# CON1.net
KiCad netlist of a schematic drawn in Altium Designer
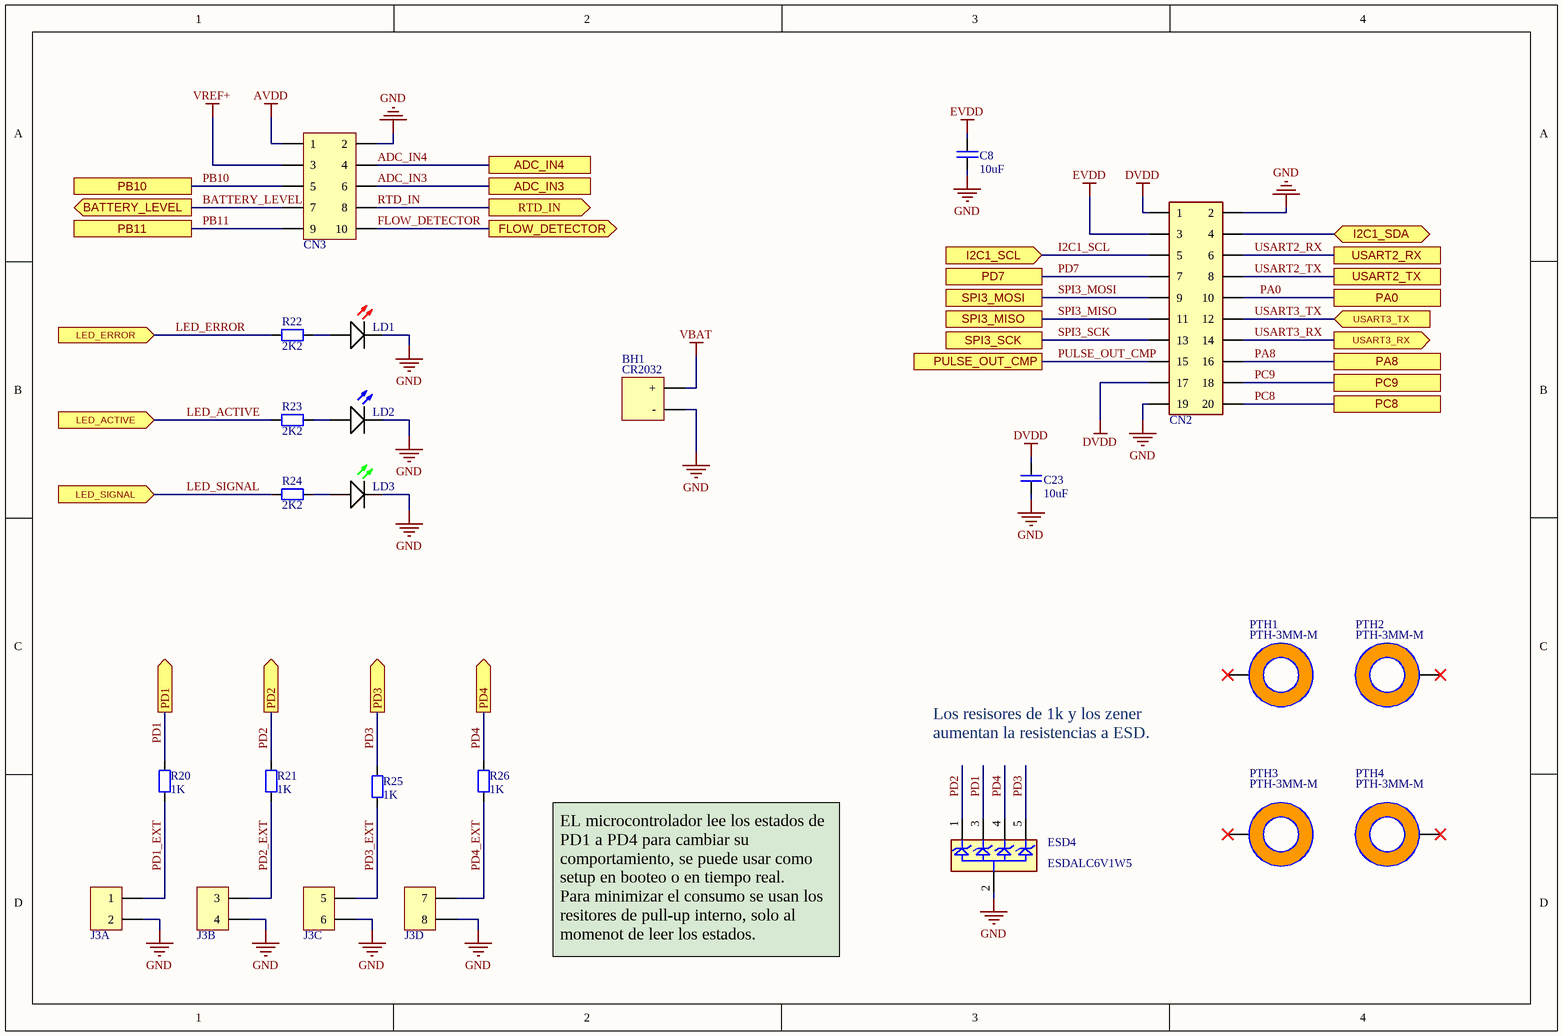
[diagram p0: CON1.SchDoc]

(export (version "E")
  (design (tool "Eeschema 10.0.6"))
  (components
    (comp (ref "BH1")
      (value "CR2032")
      (footprint "BS-08-B2AA016")
      (description "Battery base -25℃~+85℃ CR2032 SMD Battery Connectors ROHS")
      (fields
        (field (name "MANUFACTURER") "Myoung")
        (field (name "MANUFACTURER PART NUMBER") "BS-08-B2AA016")
      )
      (libsource (lib "Battery_Holders") (part "BS-08-B2AA016"))
    )
    (comp (ref "C8")
      (value "10uF")
      (footprint "CAP_SM0805_YAGEOCC2_N")
      (description "CAP 10uF SM0805 X5R 25V YAGEO")
      (fields
        (field (name "MANUFACTURER") "Yageo")
        (field (name "MANUFACTURER PART NUMBER") "CC0805KKX5R8BB106")
      )
      (libsource (lib "Yageo") (part "CC0805KKX5R8BB106"))
    )
    (comp (ref "C23")
      (value "10uF")
      (footprint "CAP_SM0805_YAGEOCC2_N")
      (description "CAP 10uF SM0805 X5R 25V YAGEO")
      (fields
        (field (name "MANUFACTURER") "Yageo")
        (field (name "MANUFACTURER PART NUMBER") "CC0805KKX5R8BB106")
      )
      (libsource (lib "Yageo") (part "CC0805KKX5R8BB106"))
    )
    (comp (ref "CN2")
      (value "DW254R-22-20-85")
      (footprint "DW254R-22-10-85")
      (description "2 x 10 - true hole 2.54mm - altura 8.5mm")
      (fields (field (name "MANUFACTURER") "Dealon"))
      (libsource (lib "header_female") (part "DW254R-22-20-85"))
    )
    (comp (ref "CN3")
      (value "DW254S-22-10-85")
      (footprint "2X5 100 MILS SMD")
      (description "2 x 5 - SMD 2.54mm - altura 8.5mm")
      (fields (field (name "MANUFACTURER") "Dealon"))
      (libsource (lib "header_female") (part "DW254S-22-10-85"))
    )
    (comp (ref "ESD4")
      (value "ESDALC6V1W5")
      (footprint "ESDALC6V1W5")
      (fields (field (name "MANUFACTURER") "ST"))
      (libsource (lib "diode") (part "ESDALC6V1W5"))
    )
    (comp (ref "J3")
      (value "PH2.54-07-04PWS-JUMPER")
      (footprint "HEADER PIN 2X4 A 90 GRADOS")
      (description "2 x 4 - true hole  2.54mm 90°")
      (fields
        (field (name "MANUFACTURER") "XUNPU")
        (field (name "MANUFACTURER PART NUMBER") "PH2.54-07-04PWS")
      )
      (libsource (lib "header_pin") (part "PH2.54-07-04PWS-JUMPER"))
    )
    (comp (ref "LD1")
      (value "ERROR")
      (footprint "LED 0805")
      (fields
        (field (name "MANUFACTURER") "Everlight Elec")
        (field (name "MANUFACTURER PART NUMBER") "17-21SURC/S530-A2/TR8")
      )
      (libsource (lib "LED") (part "17-21SURC/S530-A2/TR8"))
    )
    (comp (ref "LD2")
      (value "RUN")
      (footprint "LED 0805")
      (fields
        (field (name "MANUFACTURER") "Everlight Elec")
        (field (name "MANUFACTURER PART NUMBER") "17-21/BHC-XL2M2TY")
      )
      (libsource (lib "LED") (part "17-21/BHC-XL2M2TY/3T"))
    )
    (comp (ref "LD3")
      (value "SGINAL")
      (footprint "LED 0805")
      (fields
        (field (name "MANUFACTURER") "Everlight Elec")
        (field (name "MANUFACTURER PART NUMBER") "17-21SYGC/S530-E2/TR8")
      )
      (libsource (lib "LED") (part "17-21SYGC/S530-E2/TR8"))
    )
    (comp (ref "PTH1")
      (value "PTH-3MM-M")
      (footprint "PTH_M3_M")
      (description "Agujero de montaje metalizado roscas M3. Drill de tamaño medio.")
      (libsource (lib "montaje") (part "PTH-3MM-M"))
    )
    (comp (ref "PTH2")
      (value "PTH-3MM-M")
      (footprint "PTH_M3_M")
      (description "Agujero de montaje metalizado roscas M3. Drill de tamaño medio.")
      (libsource (lib "montaje") (part "PTH-3MM-M"))
    )
    (comp (ref "PTH3")
      (value "PTH-3MM-M")
      (footprint "PTH_M3_M")
      (description "Agujero de montaje metalizado roscas M3. Drill de tamaño medio.")
      (libsource (lib "montaje") (part "PTH-3MM-M"))
    )
    (comp (ref "PTH4")
      (value "PTH-3MM-M")
      (footprint "PTH_M3_M")
      (description "Agujero de montaje metalizado roscas M3. Drill de tamaño medio.")
      (libsource (lib "montaje") (part "PTH-3MM-M"))
    )
    (comp (ref "R20")
      (value "1K")
      (footprint "RES_SM0805_YAGEORC_N")
      (description "RES 1K SM0805 YAGEO RC_L")
      (fields
        (field (name "MANUFACTURER") "Yageo")
        (field (name "MANUFACTURER PART NUMBER") "RC0805FR-071KL")
      )
      (libsource (lib "Yageo") (part "RC0805FR-071KL"))
    )
    (comp (ref "R21")
      (value "1K")
      (footprint "RES_SM0805_YAGEORC_N")
      (description "RES 1K SM0805 YAGEO RC_L")
      (fields
        (field (name "MANUFACTURER") "Yageo")
        (field (name "MANUFACTURER PART NUMBER") "RC0805FR-071KL")
      )
      (libsource (lib "Yageo") (part "RC0805FR-071KL"))
    )
    (comp (ref "R22")
      (value "2K2")
      (footprint "RES_SM0805_YAGEORC_N")
      (description "RES 2K2 SM0805 YAGEO RC_L")
      (fields
        (field (name "MANUFACTURER") "Yageo")
        (field (name "MANUFACTURER PART NUMBER") "RC0805FR-072K2L")
      )
      (libsource (lib "Yageo") (part "RC0805FR-072K2L"))
    )
    (comp (ref "R23")
      (value "2K2")
      (footprint "RES_SM0805_YAGEORC_N")
      (description "RES 2K2 SM0805 YAGEO RC_L")
      (fields
        (field (name "MANUFACTURER") "Yageo")
        (field (name "MANUFACTURER PART NUMBER") "RC0805FR-072K2L")
      )
      (libsource (lib "Yageo") (part "RC0805FR-072K2L"))
    )
    (comp (ref "R24")
      (value "2K2")
      (footprint "RES_SM0805_YAGEORC_N")
      (description "RES 2K2 SM0805 YAGEO RC_L")
      (fields
        (field (name "MANUFACTURER") "Yageo")
        (field (name "MANUFACTURER PART NUMBER") "RC0805FR-072K2L")
      )
      (libsource (lib "Yageo") (part "RC0805FR-072K2L"))
    )
    (comp (ref "R25")
      (value "1K")
      (footprint "RES_SM0805_YAGEORC_N")
      (description "RES 1K SM0805 YAGEO RC_L")
      (fields
        (field (name "MANUFACTURER") "Yageo")
        (field (name "MANUFACTURER PART NUMBER") "RC0805FR-071KL")
      )
      (libsource (lib "Yageo") (part "RC0805FR-071KL"))
    )
    (comp (ref "R26")
      (value "1K")
      (footprint "RES_SM0805_YAGEORC_N")
      (description "RES 1K SM0805 YAGEO RC_L")
      (fields
        (field (name "MANUFACTURER") "Yageo")
        (field (name "MANUFACTURER PART NUMBER") "RC0805FR-071KL")
      )
      (libsource (lib "Yageo") (part "RC0805FR-071KL"))
    )
  )
  (nets
    (net (code "1") (name "/ADC_IN3") (class "Default")
      (node (ref "CN3") (pin "6") (pinfunction "6_6") (pintype "passive"))
    )
    (net (code "2") (name "/ADC_IN4") (class "Default")
      (node (ref "CN3") (pin "4") (pinfunction "4_4") (pintype "passive"))
    )
    (net (code "3") (name "/BATTERY_LEVEL") (class "Default")
      (node (ref "CN3") (pin "7") (pinfunction "7_7") (pintype "passive"))
    )
    (net (code "4") (name "/FLOW_DETECTOR") (class "Default")
      (node (ref "CN3") (pin "10") (pinfunction "10_10") (pintype "passive"))
    )
    (net (code "5") (name "/I2C1_SCL") (class "Default")
      (node (ref "CN2") (pin "5") (pinfunction "5_5") (pintype "passive"))
    )
    (net (code "6") (name "/I2C1_SDA") (class "Default")
      (node (ref "CN2") (pin "4") (pinfunction "4_4") (pintype "passive"))
    )
    (net (code "7") (name "/LED_ACTIVE") (class "Default") (node (ref "R23") (pin "1") (pintype "passive")))
    (net (code "8") (name "/LED_ERROR") (class "Default") (node (ref "R22") (pin "1") (pintype "passive")))
    (net (code "9") (name "/LED_SIGNAL") (class "Default") (node (ref "R24") (pin "1") (pintype "passive")))
    (net (code "10") (name "/PA0") (class "Default")
      (node (ref "CN2") (pin "10") (pinfunction "10_10") (pintype "passive"))
    )
    (net (code "11") (name "/PA8") (class "Default")
      (node (ref "CN2") (pin "16") (pinfunction "16_16") (pintype "passive"))
    )
    (net (code "12") (name "/PB10") (class "Default")
      (node (ref "CN3") (pin "5") (pinfunction "5_5") (pintype "passive"))
    )
    (net (code "13") (name "/PB11") (class "Default")
      (node (ref "CN3") (pin "9") (pinfunction "9_9") (pintype "passive"))
    )
    (net (code "14") (name "/PC8") (class "Default")
      (node (ref "CN2") (pin "20") (pinfunction "20_20") (pintype "passive"))
    )
    (net (code "15") (name "/PC9") (class "Default")
      (node (ref "CN2") (pin "18") (pinfunction "18_18") (pintype "passive"))
    )
    (net (code "16") (name "/PD1") (class "Default")
      (node (ref "ESD4") (pin "3") (pinfunction "I/02_3") (pintype "passive"))
      (node (ref "R20") (pin "2") (pintype "passive"))
    )
    (net (code "17") (name "/PD1_EXT") (class "Default")
      (node (ref "J3") (pin "1") (pinfunction "1_1") (pintype "passive"))
      (node (ref "R20") (pin "1") (pintype "passive"))
    )
    (net (code "18") (name "/PD2") (class "Default")
      (node (ref "ESD4") (pin "1") (pinfunction "I/01_1") (pintype "passive"))
      (node (ref "R21") (pin "2") (pintype "passive"))
    )
    (net (code "19") (name "/PD2_EXT") (class "Default")
      (node (ref "J3") (pin "3") (pinfunction "3_3") (pintype "passive"))
      (node (ref "R21") (pin "1") (pintype "passive"))
    )
    (net (code "20") (name "/PD3") (class "Default")
      (node (ref "ESD4") (pin "5") (pinfunction "I/04_5") (pintype "passive"))
      (node (ref "R25") (pin "2") (pintype "passive"))
    )
    (net (code "21") (name "/PD3_EXT") (class "Default")
      (node (ref "J3") (pin "5") (pinfunction "5_5") (pintype "passive"))
      (node (ref "R25") (pin "1") (pintype "passive"))
    )
    (net (code "22") (name "/PD4") (class "Default")
      (node (ref "ESD4") (pin "4") (pinfunction "I/03_4") (pintype "passive"))
      (node (ref "R26") (pin "2") (pintype "passive"))
    )
    (net (code "23") (name "/PD4_EXT") (class "Default")
      (node (ref "J3") (pin "7") (pinfunction "7_7") (pintype "passive"))
      (node (ref "R26") (pin "1") (pintype "passive"))
    )
    (net (code "24") (name "/PD7") (class "Default")
      (node (ref "CN2") (pin "7") (pinfunction "7_7") (pintype "passive"))
    )
    (net (code "25") (name "/PULSE_OUT_CMP") (class "Default")
      (node (ref "CN2") (pin "15") (pinfunction "15_15") (pintype "passive"))
    )
    (net (code "26") (name "/RTD_IN") (class "Default")
      (node (ref "CN3") (pin "8") (pinfunction "8_8") (pintype "passive"))
    )
    (net (code "27") (name "/SPI3_MISO") (class "Default")
      (node (ref "CN2") (pin "11") (pinfunction "11_11") (pintype "passive"))
    )
    (net (code "28") (name "/SPI3_MOSI") (class "Default")
      (node (ref "CN2") (pin "9") (pinfunction "9_9") (pintype "passive"))
    )
    (net (code "29") (name "/SPI3_SCK") (class "Default")
      (node (ref "CN2") (pin "13") (pinfunction "13_13") (pintype "passive"))
    )
    (net (code "30") (name "/USART2_RX") (class "Default")
      (node (ref "CN2") (pin "6") (pinfunction "6_6") (pintype "passive"))
    )
    (net (code "31") (name "/USART2_TX") (class "Default")
      (node (ref "CN2") (pin "8") (pinfunction "8_8") (pintype "passive"))
    )
    (net (code "32") (name "/USART3_RX") (class "Default")
      (node (ref "CN2") (pin "14") (pinfunction "14_14") (pintype "passive"))
    )
    (net (code "33") (name "/USART3_TX") (class "Default")
      (node (ref "CN2") (pin "12") (pinfunction "12_12") (pintype "passive"))
    )
    (net (code "34") (name "AVDD") (class "Default")
      (node (ref "CN3") (pin "1") (pinfunction "1_1") (pintype "passive"))
    )
    (net (code "35") (name "DVDD") (class "Default")
      (node (ref "C23") (pin "2") (pintype "passive"))
      (node (ref "CN2") (pin "1") (pinfunction "1_1") (pintype "passive"))
      (node (ref "CN2") (pin "17") (pinfunction "17_17") (pintype "passive"))
    )
    (net (code "36") (name "EVDD") (class "Default")
      (node (ref "C8") (pin "2") (pintype "passive"))
      (node (ref "CN2") (pin "3") (pinfunction "3_3") (pintype "passive"))
    )
    (net (code "37") (name "GND") (class "Default")
      (node (ref "BH1") (pin "NEG") (pinfunction "-_NEG") (pintype "passive"))
      (node (ref "C23") (pin "1") (pintype "passive"))
      (node (ref "C8") (pin "1") (pintype "passive"))
      (node (ref "CN2") (pin "19") (pinfunction "19_19") (pintype "passive"))
      (node (ref "CN2") (pin "2") (pinfunction "2_2") (pintype "passive"))
      (node (ref "CN3") (pin "2") (pinfunction "2_2") (pintype "passive"))
      (node (ref "ESD4") (pin "2") (pinfunction "GND_2") (pintype "passive"))
      (node (ref "J3") (pin "2") (pinfunction "2_2") (pintype "passive"))
      (node (ref "J3") (pin "4") (pinfunction "4_4") (pintype "passive"))
      (node (ref "J3") (pin "6") (pinfunction "6_6") (pintype "passive"))
      (node (ref "J3") (pin "8") (pinfunction "8_8") (pintype "passive"))
      (node (ref "LD1") (pin "K") (pinfunction "K_K") (pintype "passive"))
      (node (ref "LD2") (pin "K") (pinfunction "K_K") (pintype "passive"))
      (node (ref "LD3") (pin "K") (pinfunction "K_K") (pintype "passive"))
    )
    (net (code "38") (name "Net-(LD1-PadA)") (class "Default")
      (node (ref "LD1") (pin "A") (pinfunction "A_A") (pintype "passive"))
      (node (ref "R22") (pin "2") (pintype "passive"))
    )
    (net (code "39") (name "Net-(LD2-PadA)") (class "Default")
      (node (ref "LD2") (pin "A") (pinfunction "A_A") (pintype "passive"))
      (node (ref "R23") (pin "2") (pintype "passive"))
    )
    (net (code "40") (name "Net-(LD3-PadA)") (class "Default")
      (node (ref "LD3") (pin "A") (pinfunction "A_A") (pintype "passive"))
      (node (ref "R24") (pin "2") (pintype "passive"))
    )
    (net (code "41") (name "VBAT") (class "Default")
      (node (ref "BH1") (pin "POS") (pinfunction "+_POS") (pintype "passive"))
    )
    (net (code "42") (name "VREF+") (class "Default")
      (node (ref "CN3") (pin "3") (pinfunction "3_3") (pintype "passive"))
    )
    (net (code "43") (name "unconnected-(PTH1-Pad1)") (class "Default")
      (node (ref "PTH1") (pin "1") (pinfunction "1_1") (pintype "passive+no_connect"))
    )
    (net (code "44") (name "unconnected-(PTH2-Pad1)") (class "Default")
      (node (ref "PTH2") (pin "1") (pinfunction "1_1") (pintype "passive+no_connect"))
    )
    (net (code "45") (name "unconnected-(PTH3-Pad1)") (class "Default")
      (node (ref "PTH3") (pin "1") (pinfunction "1_1") (pintype "passive+no_connect"))
    )
    (net (code "46") (name "unconnected-(PTH4-Pad1)") (class "Default")
      (node (ref "PTH4") (pin "1") (pinfunction "1_1") (pintype "passive+no_connect"))
    )
  )
)
